# Schematic.net
KiCad netlist of a schematic drawn in Altium Designer
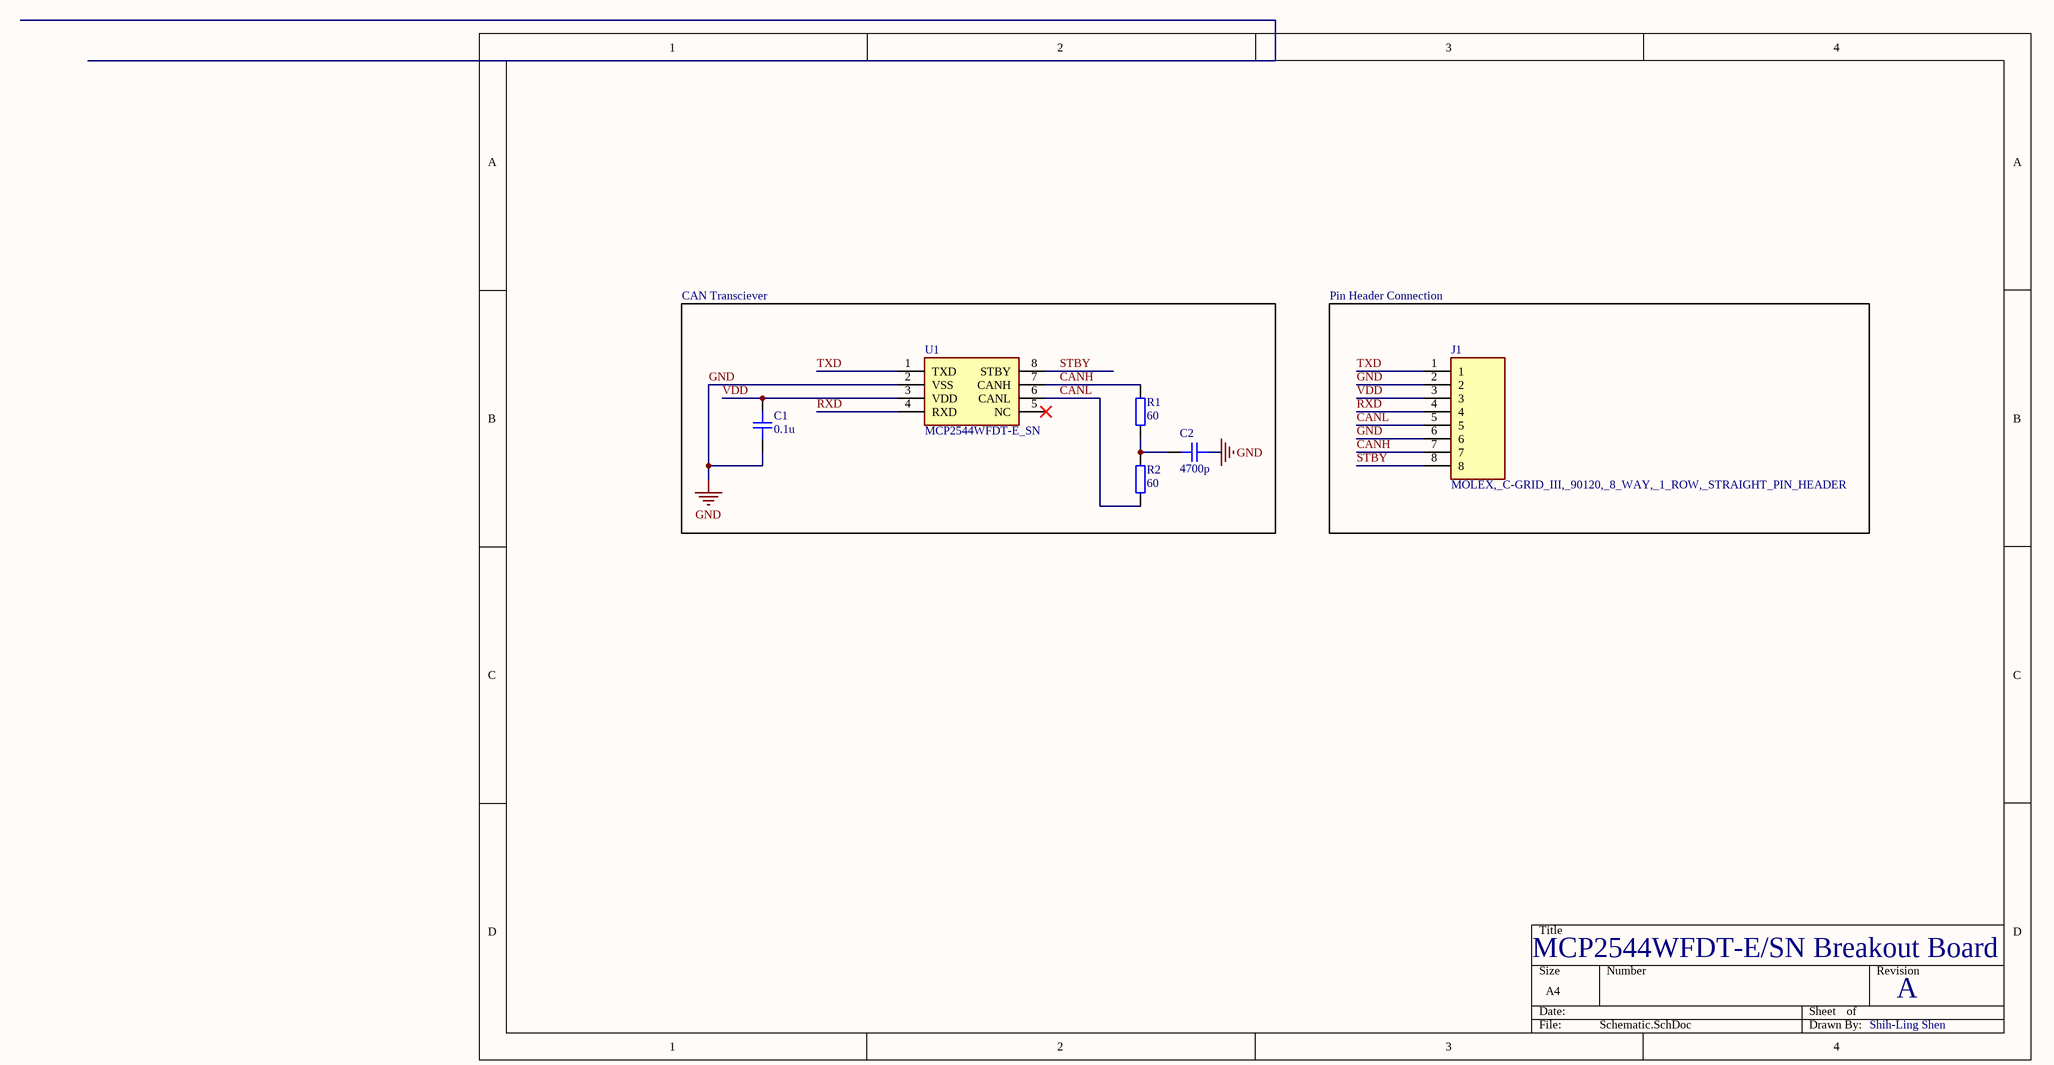
[diagram p0: Schematic.SchDoc]

(export (version "E")
  (design (tool "Eeschema 10.0.6"))
  (components
    (comp (ref "C1")
      (value "0.1u")
      (footprint "CAP_0402")
      (description "Capacitor SMD 0402 10V")
      (libsource (lib "Schematic-Lib-PhilsLab") (part "CAP_0402_10V"))
    )
    (comp (ref "C2")
      (value "4700p")
      (footprint "CAP_0402")
      (description "Capacitor SMD 0402 10V")
      (libsource (lib "Schematic-Lib-PhilsLab") (part "CAP_0402_10V"))
    )
    (comp (ref "J1")
      (value "MOLEX,_C-GRID_III,_90120,_8_WAY,_1_ROW,_STRAIGHT_PIN_HEADER")
      (footprint "SamacSys:HDRV8W65P0X254_1X8_2010X249X945P")
      (description "Connector")
      (fields (field (name "MANUFACTURER_PART_NUMBER") "MOLEX"))
      (libsource (lib "*") (part "MOLEX,_C-GRID_III,_90120,_8_WAY,_1_ROW,_STRAIGHT_PIN_HEADER"))
    )
    (comp (ref "R1")
      (value "60")
      (footprint "RES_0805")
      (description "Resistor SMD 0805")
      (libsource (lib "Schematic-Lib-PhilsLab") (part "RES_0805"))
    )
    (comp (ref "R2")
      (value "60")
      (footprint "RES_0805")
      (description "Resistor SMD 0805")
      (libsource (lib "Schematic-Lib-PhilsLab") (part "RES_0805"))
    )
    (comp (ref "U1")
      (value "MCP2544WFDT-E_SN")
      (footprint "SamacSys:SOIC127P600X175-8N")
      (description "Integrated Circuit")
      (fields
        (field (name "MANUFACTURER_PART_NUMBER") "MCP2544WFDT-E/SN")
        (field (name "MOUSER PART NUMBER") "579-MCP2544WFDT-E/SN")
      )
      (libsource (lib "*") (part "MCP2544WFDT-E_SN"))
    )
  )
  (nets
    (net (code "1") (name "/CANH") (class "Default")
      (node (ref "J1") (pin "7") (pinfunction "7_7") (pintype "passive"))
      (node (ref "R1") (pin "2") (pinfunction "2_2") (pintype "passive"))
      (node (ref "U1") (pin "7") (pinfunction "CANH_7") (pintype "passive"))
    )
    (net (code "2") (name "/CANL") (class "Default")
      (node (ref "J1") (pin "5") (pinfunction "5_5") (pintype "passive"))
      (node (ref "R2") (pin "1") (pinfunction "1_1") (pintype "passive"))
      (node (ref "U1") (pin "6") (pinfunction "CANL_6") (pintype "passive"))
    )
    (net (code "3") (name "/RXD") (class "Default")
      (node (ref "J1") (pin "4") (pinfunction "4_4") (pintype "passive"))
      (node (ref "U1") (pin "4") (pinfunction "RXD_4") (pintype "passive"))
    )
    (net (code "4") (name "/STBY") (class "Default")
      (node (ref "J1") (pin "8") (pinfunction "8_8") (pintype "passive"))
      (node (ref "U1") (pin "8") (pinfunction "STBY_8") (pintype "passive"))
    )
    (net (code "5") (name "/TXD") (class "Default")
      (node (ref "J1") (pin "1") (pinfunction "1_1") (pintype "passive"))
      (node (ref "U1") (pin "1") (pinfunction "TXD_1") (pintype "passive"))
    )
    (net (code "6") (name "/VDD") (class "Default")
      (node (ref "C1") (pin "1") (pinfunction "1_1") (pintype "passive"))
      (node (ref "J1") (pin "3") (pinfunction "3_3") (pintype "passive"))
      (node (ref "U1") (pin "3") (pinfunction "VDD_3") (pintype "passive"))
    )
    (net (code "7") (name "GND") (class "Default")
      (node (ref "C1") (pin "2") (pinfunction "2_2") (pintype "passive"))
      (node (ref "C2") (pin "2") (pinfunction "2_2") (pintype "passive"))
      (node (ref "J1") (pin "2") (pinfunction "2_2") (pintype "passive"))
      (node (ref "J1") (pin "6") (pinfunction "6_6") (pintype "passive"))
      (node (ref "U1") (pin "2") (pinfunction "VSS_2") (pintype "passive"))
    )
    (net (code "8") (name "Net-(C2-Pad1)") (class "Default")
      (node (ref "C2") (pin "1") (pinfunction "1_1") (pintype "passive"))
      (node (ref "R1") (pin "1") (pinfunction "1_1") (pintype "passive"))
      (node (ref "R2") (pin "2") (pinfunction "2_2") (pintype "passive"))
    )
    (net (code "9") (name "unconnected-(U1-NC-Pad5)") (class "Default")
      (node (ref "U1") (pin "5") (pinfunction "NC_5") (pintype "passive+no_connect"))
    )
  )
)
